# LT1990_Input2.net
KiCad netlist of a schematic drawn in Altium Designer
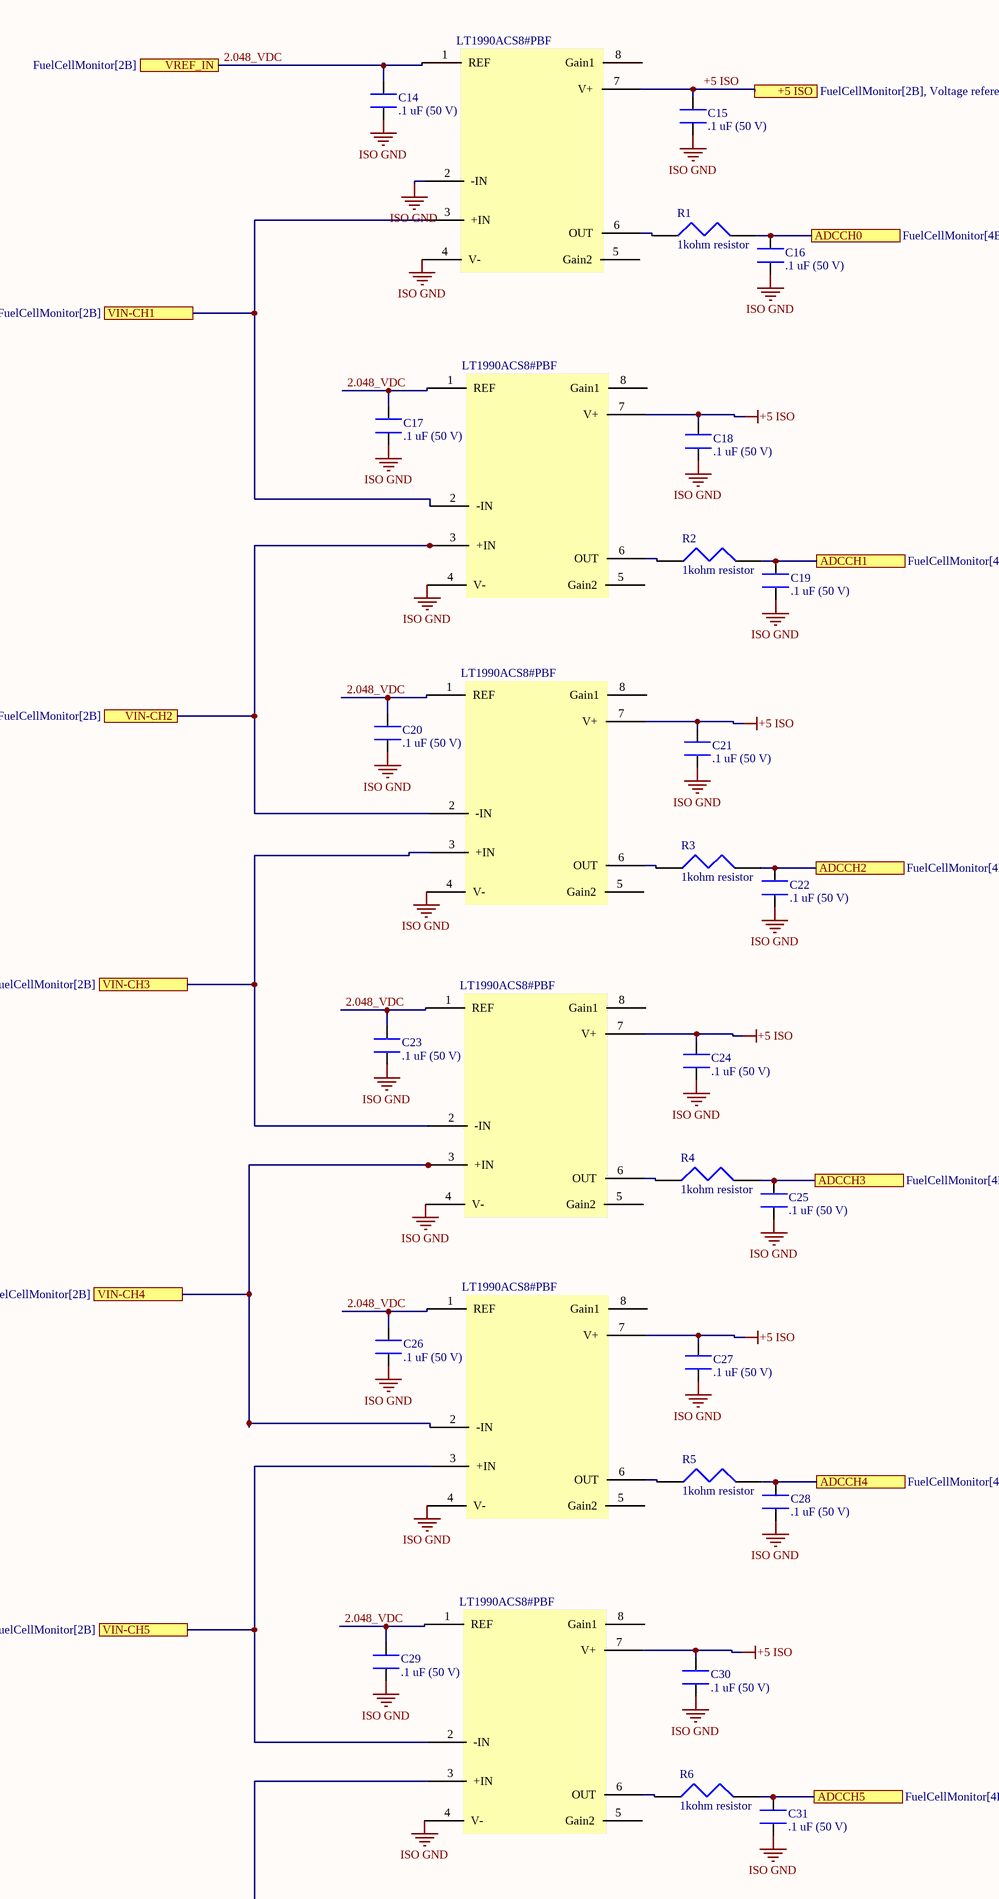
[diagram p0: LT1990(Input2).SchDoc, top left]
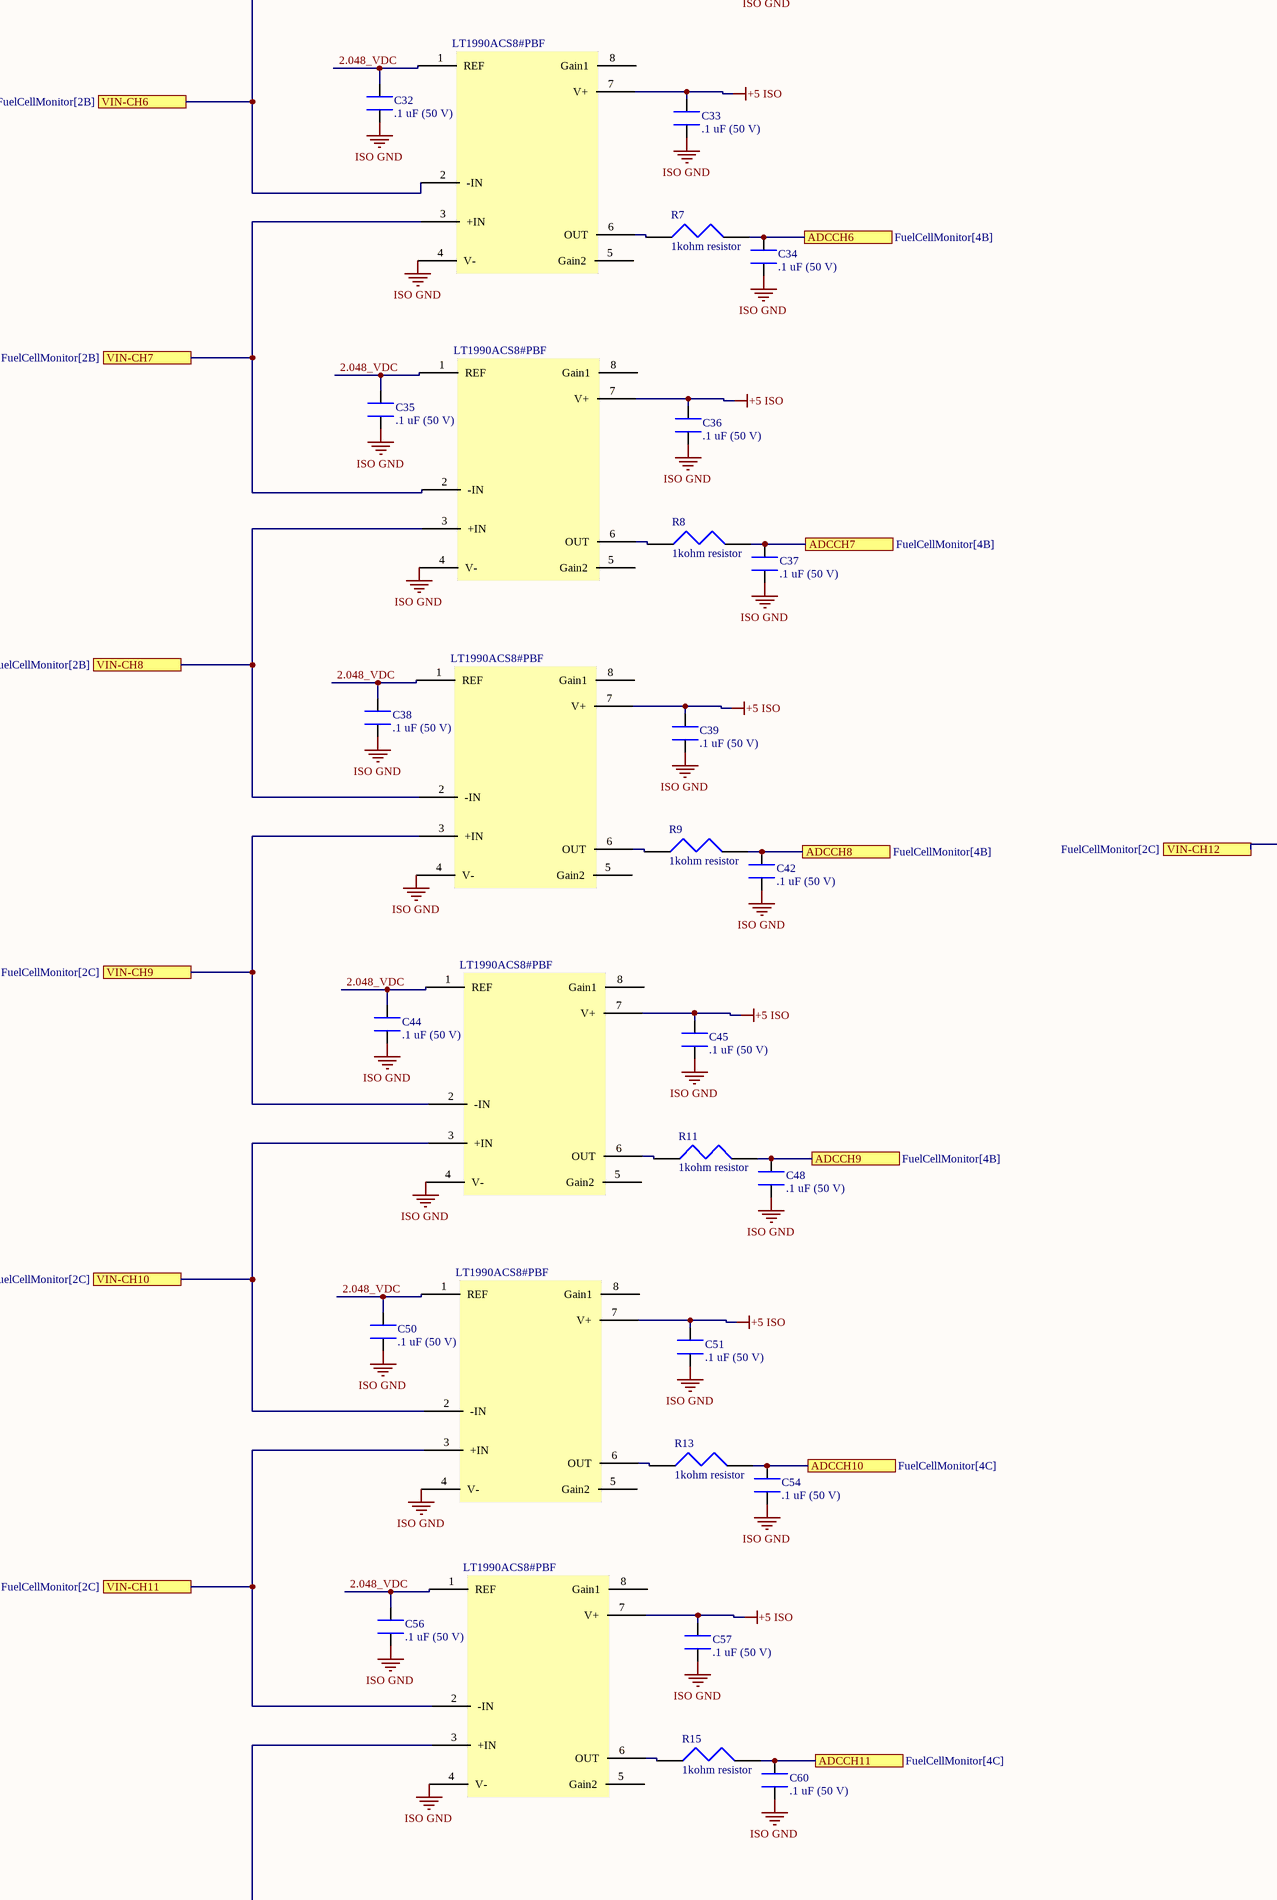
[diagram p1: LT1990(Input2).SchDoc, bottom left]
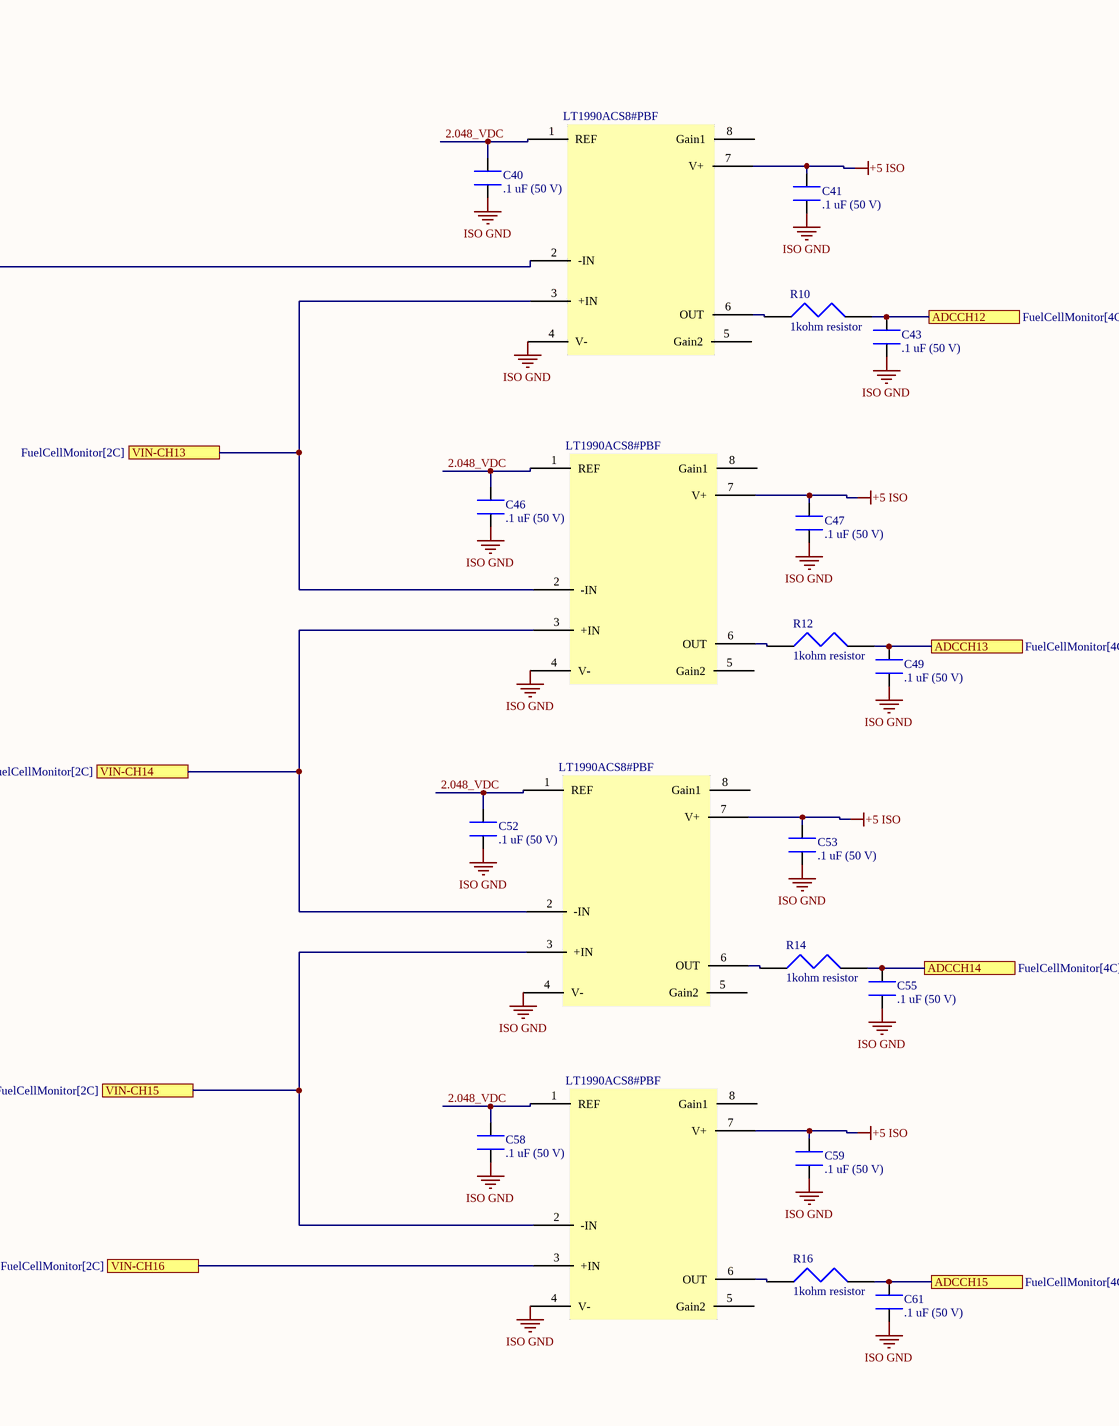
[diagram p2: LT1990(Input2).SchDoc, bottom right]

(export (version "E")
  (design (tool "Eeschema 10.0.6"))
  (components
    (comp (ref "C14")
      (value ".1 uF (50 V)")
      (footprint ".1uF capacitor")
      (libsource (lib "FuelCellMonitor") (part ".1 uF cap"))
    )
    (comp (ref "C15")
      (value ".1 uF (50 V)")
      (footprint ".1uF capacitor")
      (libsource (lib "FuelCellMonitor") (part ".1 uF cap"))
    )
    (comp (ref "C16")
      (value ".1 uF (50 V)")
      (footprint ".1uF capacitor")
      (libsource (lib "FuelCellMonitor") (part ".1 uF cap"))
    )
    (comp (ref "C17")
      (value ".1 uF (50 V)")
      (footprint ".1uF capacitor")
      (libsource (lib "FuelCellMonitor") (part ".1 uF cap"))
    )
    (comp (ref "C18")
      (value ".1 uF (50 V)")
      (footprint ".1uF capacitor")
      (libsource (lib "FuelCellMonitor") (part ".1 uF cap"))
    )
    (comp (ref "C19")
      (value ".1 uF (50 V)")
      (footprint ".1uF capacitor")
      (libsource (lib "FuelCellMonitor") (part ".1 uF cap"))
    )
    (comp (ref "C20")
      (value ".1 uF (50 V)")
      (footprint ".1uF capacitor")
      (libsource (lib "FuelCellMonitor") (part ".1 uF cap"))
    )
    (comp (ref "C21")
      (value ".1 uF (50 V)")
      (footprint ".1uF capacitor")
      (libsource (lib "FuelCellMonitor") (part ".1 uF cap"))
    )
    (comp (ref "C22")
      (value ".1 uF (50 V)")
      (footprint ".1uF capacitor")
      (libsource (lib "FuelCellMonitor") (part ".1 uF cap"))
    )
    (comp (ref "C23")
      (value ".1 uF (50 V)")
      (footprint ".1uF capacitor")
      (libsource (lib "FuelCellMonitor") (part ".1 uF cap"))
    )
    (comp (ref "C24")
      (value ".1 uF (50 V)")
      (footprint ".1uF capacitor")
      (libsource (lib "FuelCellMonitor") (part ".1 uF cap"))
    )
    (comp (ref "C25")
      (value ".1 uF (50 V)")
      (footprint ".1uF capacitor")
      (libsource (lib "FuelCellMonitor") (part ".1 uF cap"))
    )
    (comp (ref "C26")
      (value ".1 uF (50 V)")
      (footprint ".1uF capacitor")
      (libsource (lib "FuelCellMonitor") (part ".1 uF cap"))
    )
    (comp (ref "C27")
      (value ".1 uF (50 V)")
      (footprint ".1uF capacitor")
      (libsource (lib "FuelCellMonitor") (part ".1 uF cap"))
    )
    (comp (ref "C28")
      (value ".1 uF (50 V)")
      (footprint ".1uF capacitor")
      (libsource (lib "FuelCellMonitor") (part ".1 uF cap"))
    )
    (comp (ref "C29")
      (value ".1 uF (50 V)")
      (footprint ".1uF capacitor")
      (libsource (lib "FuelCellMonitor") (part ".1 uF cap"))
    )
    (comp (ref "C30")
      (value ".1 uF (50 V)")
      (footprint ".1uF capacitor")
      (libsource (lib "FuelCellMonitor") (part ".1 uF cap"))
    )
    (comp (ref "C31")
      (value ".1 uF (50 V)")
      (footprint ".1uF capacitor")
      (libsource (lib "FuelCellMonitor") (part ".1 uF cap"))
    )
    (comp (ref "C32")
      (value ".1 uF (50 V)")
      (footprint ".1uF capacitor")
      (libsource (lib "FuelCellMonitor") (part ".1 uF cap"))
    )
    (comp (ref "C33")
      (value ".1 uF (50 V)")
      (footprint ".1uF capacitor")
      (libsource (lib "FuelCellMonitor") (part ".1 uF cap"))
    )
    (comp (ref "C34")
      (value ".1 uF (50 V)")
      (footprint ".1uF capacitor")
      (libsource (lib "FuelCellMonitor") (part ".1 uF cap"))
    )
    (comp (ref "C35")
      (value ".1 uF (50 V)")
      (footprint ".1uF capacitor")
      (libsource (lib "FuelCellMonitor") (part ".1 uF cap"))
    )
    (comp (ref "C36")
      (value ".1 uF (50 V)")
      (footprint ".1uF capacitor")
      (libsource (lib "FuelCellMonitor") (part ".1 uF cap"))
    )
    (comp (ref "C37")
      (value ".1 uF (50 V)")
      (footprint ".1uF capacitor")
      (libsource (lib "FuelCellMonitor") (part ".1 uF cap"))
    )
    (comp (ref "C38")
      (value ".1 uF (50 V)")
      (footprint ".1uF capacitor")
      (libsource (lib "FuelCellMonitor") (part ".1 uF cap"))
    )
    (comp (ref "C39")
      (value ".1 uF (50 V)")
      (footprint ".1uF capacitor")
      (libsource (lib "FuelCellMonitor") (part ".1 uF cap"))
    )
    (comp (ref "C40")
      (value ".1 uF (50 V)")
      (footprint ".1uF capacitor")
      (libsource (lib "FuelCellMonitor") (part ".1 uF cap"))
    )
    (comp (ref "C41")
      (value ".1 uF (50 V)")
      (footprint ".1uF capacitor")
      (libsource (lib "FuelCellMonitor") (part ".1 uF cap"))
    )
    (comp (ref "C42")
      (value ".1 uF (50 V)")
      (footprint ".1uF capacitor")
      (libsource (lib "FuelCellMonitor") (part ".1 uF cap"))
    )
    (comp (ref "C43")
      (value ".1 uF (50 V)")
      (footprint ".1uF capacitor")
      (libsource (lib "FuelCellMonitor") (part ".1 uF cap"))
    )
    (comp (ref "C44")
      (value ".1 uF (50 V)")
      (footprint ".1uF capacitor")
      (libsource (lib "FuelCellMonitor") (part ".1 uF cap"))
    )
    (comp (ref "C45")
      (value ".1 uF (50 V)")
      (footprint ".1uF capacitor")
      (libsource (lib "FuelCellMonitor") (part ".1 uF cap"))
    )
    (comp (ref "C46")
      (value ".1 uF (50 V)")
      (footprint ".1uF capacitor")
      (libsource (lib "FuelCellMonitor") (part ".1 uF cap"))
    )
    (comp (ref "C47")
      (value ".1 uF (50 V)")
      (footprint ".1uF capacitor")
      (libsource (lib "FuelCellMonitor") (part ".1 uF cap"))
    )
    (comp (ref "C48")
      (value ".1 uF (50 V)")
      (footprint ".1uF capacitor")
      (libsource (lib "FuelCellMonitor") (part ".1 uF cap"))
    )
    (comp (ref "C49")
      (value ".1 uF (50 V)")
      (footprint ".1uF capacitor")
      (libsource (lib "FuelCellMonitor") (part ".1 uF cap"))
    )
    (comp (ref "C50")
      (value ".1 uF (50 V)")
      (footprint ".1uF capacitor")
      (libsource (lib "FuelCellMonitor") (part ".1 uF cap"))
    )
    (comp (ref "C51")
      (value ".1 uF (50 V)")
      (footprint ".1uF capacitor")
      (libsource (lib "FuelCellMonitor") (part ".1 uF cap"))
    )
    (comp (ref "C52")
      (value ".1 uF (50 V)")
      (footprint ".1uF capacitor")
      (libsource (lib "FuelCellMonitor") (part ".1 uF cap"))
    )
    (comp (ref "C53")
      (value ".1 uF (50 V)")
      (footprint ".1uF capacitor")
      (libsource (lib "FuelCellMonitor") (part ".1 uF cap"))
    )
    (comp (ref "C54")
      (value ".1 uF (50 V)")
      (footprint ".1uF capacitor")
      (libsource (lib "FuelCellMonitor") (part ".1 uF cap"))
    )
    (comp (ref "C55")
      (value ".1 uF (50 V)")
      (footprint ".1uF capacitor")
      (libsource (lib "FuelCellMonitor") (part ".1 uF cap"))
    )
    (comp (ref "C56")
      (value ".1 uF (50 V)")
      (footprint ".1uF capacitor")
      (libsource (lib "FuelCellMonitor") (part ".1 uF cap"))
    )
    (comp (ref "C57")
      (value ".1 uF (50 V)")
      (footprint ".1uF capacitor")
      (libsource (lib "FuelCellMonitor") (part ".1 uF cap"))
    )
    (comp (ref "C58")
      (value ".1 uF (50 V)")
      (footprint ".1uF capacitor")
      (libsource (lib "FuelCellMonitor") (part ".1 uF cap"))
    )
    (comp (ref "C59")
      (value ".1 uF (50 V)")
      (footprint ".1uF capacitor")
      (libsource (lib "FuelCellMonitor") (part ".1 uF cap"))
    )
    (comp (ref "C60")
      (value ".1 uF (50 V)")
      (footprint ".1uF capacitor")
      (libsource (lib "FuelCellMonitor") (part ".1 uF cap"))
    )
    (comp (ref "C61")
      (value ".1 uF (50 V)")
      (footprint ".1uF capacitor")
      (libsource (lib "FuelCellMonitor") (part ".1 uF cap"))
    )
    (comp (ref "LT1")
      (value "LT1990")
      (footprint "LT1990ACS8")
      (libsource (lib "FuelCellMonitor") (part "LT1990"))
    )
    (comp (ref "LT2")
      (value "LT1990")
      (footprint "LT1990ACS8")
      (libsource (lib "FuelCellMonitor") (part "LT1990"))
    )
    (comp (ref "LT3")
      (value "LT1990")
      (footprint "LT1990ACS8")
      (libsource (lib "FuelCellMonitor") (part "LT1990"))
    )
    (comp (ref "LT4")
      (value "LT1990")
      (footprint "LT1990ACS8")
      (libsource (lib "FuelCellMonitor") (part "LT1990"))
    )
    (comp (ref "LT5")
      (value "LT1990")
      (footprint "LT1990ACS8")
      (libsource (lib "FuelCellMonitor") (part "LT1990"))
    )
    (comp (ref "LT6")
      (value "LT1990")
      (footprint "LT1990ACS8")
      (libsource (lib "FuelCellMonitor") (part "LT1990"))
    )
    (comp (ref "LT7")
      (value "LT1990")
      (footprint "LT1990ACS8")
      (libsource (lib "FuelCellMonitor") (part "LT1990"))
    )
    (comp (ref "LT8")
      (value "LT1990")
      (footprint "LT1990ACS8")
      (libsource (lib "FuelCellMonitor") (part "LT1990"))
    )
    (comp (ref "LT9")
      (value "LT1990")
      (footprint "LT1990ACS8")
      (libsource (lib "FuelCellMonitor") (part "LT1990"))
    )
    (comp (ref "LT10")
      (value "LT1990")
      (footprint "LT1990ACS8")
      (libsource (lib "FuelCellMonitor") (part "LT1990"))
    )
    (comp (ref "LT11")
      (value "LT1990")
      (footprint "LT1990ACS8")
      (libsource (lib "FuelCellMonitor") (part "LT1990"))
    )
    (comp (ref "LT12")
      (value "LT1990")
      (footprint "LT1990ACS8")
      (libsource (lib "FuelCellMonitor") (part "LT1990"))
    )
    (comp (ref "LT13")
      (value "LT1990")
      (footprint "LT1990ACS8")
      (libsource (lib "FuelCellMonitor") (part "LT1990"))
    )
    (comp (ref "LT14")
      (value "LT1990")
      (footprint "LT1990ACS8")
      (libsource (lib "FuelCellMonitor") (part "LT1990"))
    )
    (comp (ref "LT15")
      (value "LT1990")
      (footprint "LT1990ACS8")
      (libsource (lib "FuelCellMonitor") (part "LT1990"))
    )
    (comp (ref "LT16")
      (value "LT1990")
      (footprint "LT1990ACS8")
      (libsource (lib "FuelCellMonitor") (part "LT1990"))
    )
    (comp (ref "R1")
      (value "1kohm resistor")
      (footprint "1kohm resistor")
      (libsource (lib "FuelCellMonitor") (part "1kohm resistor"))
    )
    (comp (ref "R2")
      (value "1kohm resistor")
      (footprint "1kohm resistor")
      (libsource (lib "FuelCellMonitor") (part "1kohm resistor"))
    )
    (comp (ref "R3")
      (value "1kohm resistor")
      (footprint "1kohm resistor")
      (libsource (lib "FuelCellMonitor") (part "1kohm resistor"))
    )
    (comp (ref "R4")
      (value "1kohm resistor")
      (footprint "1kohm resistor")
      (libsource (lib "FuelCellMonitor") (part "1kohm resistor"))
    )
    (comp (ref "R5")
      (value "1kohm resistor")
      (footprint "1kohm resistor")
      (libsource (lib "FuelCellMonitor") (part "1kohm resistor"))
    )
    (comp (ref "R6")
      (value "1kohm resistor")
      (footprint "1kohm resistor")
      (libsource (lib "FuelCellMonitor") (part "1kohm resistor"))
    )
    (comp (ref "R7")
      (value "1kohm resistor")
      (footprint "1kohm resistor")
      (libsource (lib "FuelCellMonitor") (part "1kohm resistor"))
    )
    (comp (ref "R8")
      (value "1kohm resistor")
      (footprint "1kohm resistor")
      (libsource (lib "FuelCellMonitor") (part "1kohm resistor"))
    )
    (comp (ref "R9")
      (value "1kohm resistor")
      (footprint "1kohm resistor")
      (libsource (lib "FuelCellMonitor") (part "1kohm resistor"))
    )
    (comp (ref "R10")
      (value "1kohm resistor")
      (footprint "1kohm resistor")
      (libsource (lib "FuelCellMonitor") (part "1kohm resistor"))
    )
    (comp (ref "R11")
      (value "1kohm resistor")
      (footprint "1kohm resistor")
      (libsource (lib "FuelCellMonitor") (part "1kohm resistor"))
    )
    (comp (ref "R12")
      (value "1kohm resistor")
      (footprint "1kohm resistor")
      (libsource (lib "FuelCellMonitor") (part "1kohm resistor"))
    )
    (comp (ref "R13")
      (value "1kohm resistor")
      (footprint "1kohm resistor")
      (libsource (lib "FuelCellMonitor") (part "1kohm resistor"))
    )
    (comp (ref "R14")
      (value "1kohm resistor")
      (footprint "1kohm resistor")
      (libsource (lib "FuelCellMonitor") (part "1kohm resistor"))
    )
    (comp (ref "R15")
      (value "1kohm resistor")
      (footprint "1kohm resistor")
      (libsource (lib "FuelCellMonitor") (part "1kohm resistor"))
    )
    (comp (ref "R16")
      (value "1kohm resistor")
      (footprint "1kohm resistor")
      (libsource (lib "FuelCellMonitor") (part "1kohm resistor"))
    )
  )
  (nets
    (net (code "1") (name "+5 ISO") (class "Default")
      (node (ref "C15") (pin "2") (pinfunction "2_2") (pintype "power_in"))
      (node (ref "C18") (pin "2") (pinfunction "2_2") (pintype "power_in"))
      (node (ref "C21") (pin "2") (pinfunction "2_2") (pintype "power_in"))
      (node (ref "C24") (pin "2") (pinfunction "2_2") (pintype "power_in"))
      (node (ref "C27") (pin "2") (pinfunction "2_2") (pintype "power_in"))
      (node (ref "C30") (pin "2") (pinfunction "2_2") (pintype "power_in"))
      (node (ref "C33") (pin "2") (pinfunction "2_2") (pintype "power_in"))
      (node (ref "C36") (pin "2") (pinfunction "2_2") (pintype "power_in"))
      (node (ref "C39") (pin "2") (pinfunction "2_2") (pintype "power_in"))
      (node (ref "C41") (pin "2") (pinfunction "2_2") (pintype "power_in"))
      (node (ref "C45") (pin "2") (pinfunction "2_2") (pintype "power_in"))
      (node (ref "C47") (pin "2") (pinfunction "2_2") (pintype "power_in"))
      (node (ref "C51") (pin "2") (pinfunction "2_2") (pintype "power_in"))
      (node (ref "C53") (pin "2") (pinfunction "2_2") (pintype "power_in"))
      (node (ref "C57") (pin "2") (pinfunction "2_2") (pintype "power_in"))
      (node (ref "C59") (pin "2") (pinfunction "2_2") (pintype "power_in"))
      (node (ref "LT1") (pin "7") (pinfunction "V+_7") (pintype "passive"))
      (node (ref "LT10") (pin "7") (pinfunction "V+_7") (pintype "passive"))
      (node (ref "LT11") (pin "7") (pinfunction "V+_7") (pintype "passive"))
      (node (ref "LT12") (pin "7") (pinfunction "V+_7") (pintype "passive"))
      (node (ref "LT13") (pin "7") (pinfunction "V+_7") (pintype "passive"))
      (node (ref "LT14") (pin "7") (pinfunction "V+_7") (pintype "passive"))
      (node (ref "LT15") (pin "7") (pinfunction "V+_7") (pintype "passive"))
      (node (ref "LT16") (pin "7") (pinfunction "V+_7") (pintype "passive"))
      (node (ref "LT2") (pin "7") (pinfunction "V+_7") (pintype "passive"))
      (node (ref "LT3") (pin "7") (pinfunction "V+_7") (pintype "passive"))
      (node (ref "LT4") (pin "7") (pinfunction "V+_7") (pintype "passive"))
      (node (ref "LT5") (pin "7") (pinfunction "V+_7") (pintype "passive"))
      (node (ref "LT6") (pin "7") (pinfunction "V+_7") (pintype "passive"))
      (node (ref "LT7") (pin "7") (pinfunction "V+_7") (pintype "passive"))
      (node (ref "LT8") (pin "7") (pinfunction "V+_7") (pintype "passive"))
      (node (ref "LT9") (pin "7") (pinfunction "V+_7") (pintype "passive"))
    )
    (net (code "2") (name "/2.048_VDC") (class "Default")
      (node (ref "C14") (pin "2") (pinfunction "2_2") (pintype "power_in"))
      (node (ref "C17") (pin "2") (pinfunction "2_2") (pintype "power_in"))
      (node (ref "C20") (pin "2") (pinfunction "2_2") (pintype "power_in"))
      (node (ref "C23") (pin "2") (pinfunction "2_2") (pintype "power_in"))
      (node (ref "C26") (pin "2") (pinfunction "2_2") (pintype "power_in"))
      (node (ref "C29") (pin "2") (pinfunction "2_2") (pintype "power_in"))
      (node (ref "C32") (pin "2") (pinfunction "2_2") (pintype "power_in"))
      (node (ref "C35") (pin "2") (pinfunction "2_2") (pintype "power_in"))
      (node (ref "C38") (pin "2") (pinfunction "2_2") (pintype "power_in"))
      (node (ref "C40") (pin "2") (pinfunction "2_2") (pintype "power_in"))
      (node (ref "C44") (pin "2") (pinfunction "2_2") (pintype "power_in"))
      (node (ref "C46") (pin "2") (pinfunction "2_2") (pintype "power_in"))
      (node (ref "C50") (pin "2") (pinfunction "2_2") (pintype "power_in"))
      (node (ref "C52") (pin "2") (pinfunction "2_2") (pintype "power_in"))
      (node (ref "C56") (pin "2") (pinfunction "2_2") (pintype "power_in"))
      (node (ref "C58") (pin "2") (pinfunction "2_2") (pintype "power_in"))
      (node (ref "LT1") (pin "1") (pinfunction "REF_1") (pintype "passive"))
      (node (ref "LT10") (pin "1") (pinfunction "REF_1") (pintype "passive"))
      (node (ref "LT11") (pin "1") (pinfunction "REF_1") (pintype "passive"))
      (node (ref "LT12") (pin "1") (pinfunction "REF_1") (pintype "passive"))
      (node (ref "LT13") (pin "1") (pinfunction "REF_1") (pintype "passive"))
      (node (ref "LT14") (pin "1") (pinfunction "REF_1") (pintype "passive"))
      (node (ref "LT15") (pin "1") (pinfunction "REF_1") (pintype "passive"))
      (node (ref "LT16") (pin "1") (pinfunction "REF_1") (pintype "passive"))
      (node (ref "LT2") (pin "1") (pinfunction "REF_1") (pintype "passive"))
      (node (ref "LT3") (pin "1") (pinfunction "REF_1") (pintype "passive"))
      (node (ref "LT4") (pin "1") (pinfunction "REF_1") (pintype "passive"))
      (node (ref "LT5") (pin "1") (pinfunction "REF_1") (pintype "passive"))
      (node (ref "LT6") (pin "1") (pinfunction "REF_1") (pintype "passive"))
      (node (ref "LT7") (pin "1") (pinfunction "REF_1") (pintype "passive"))
      (node (ref "LT8") (pin "1") (pinfunction "REF_1") (pintype "passive"))
      (node (ref "LT9") (pin "1") (pinfunction "REF_1") (pintype "passive"))
    )
    (net (code "3") (name "/ADCCH0") (class "Default")
      (node (ref "C16") (pin "2") (pinfunction "2_2") (pintype "power_in"))
      (node (ref "R1") (pin "2") (pinfunction "2_2") (pintype "passive"))
    )
    (net (code "4") (name "/ADCCH1") (class "Default")
      (node (ref "C19") (pin "2") (pinfunction "2_2") (pintype "power_in"))
      (node (ref "R2") (pin "2") (pinfunction "2_2") (pintype "passive"))
    )
    (net (code "5") (name "/ADCCH2") (class "Default")
      (node (ref "C22") (pin "2") (pinfunction "2_2") (pintype "power_in"))
      (node (ref "R3") (pin "2") (pinfunction "2_2") (pintype "passive"))
    )
    (net (code "6") (name "/ADCCH3") (class "Default")
      (node (ref "C25") (pin "2") (pinfunction "2_2") (pintype "power_in"))
      (node (ref "R4") (pin "2") (pinfunction "2_2") (pintype "passive"))
    )
    (net (code "7") (name "/ADCCH4") (class "Default")
      (node (ref "C28") (pin "2") (pinfunction "2_2") (pintype "power_in"))
      (node (ref "R5") (pin "2") (pinfunction "2_2") (pintype "passive"))
    )
    (net (code "8") (name "/ADCCH5") (class "Default")
      (node (ref "C31") (pin "2") (pinfunction "2_2") (pintype "power_in"))
      (node (ref "R6") (pin "2") (pinfunction "2_2") (pintype "passive"))
    )
    (net (code "9") (name "/ADCCH6") (class "Default")
      (node (ref "C34") (pin "2") (pinfunction "2_2") (pintype "power_in"))
      (node (ref "R7") (pin "2") (pinfunction "2_2") (pintype "passive"))
    )
    (net (code "10") (name "/ADCCH7") (class "Default")
      (node (ref "C37") (pin "2") (pinfunction "2_2") (pintype "power_in"))
      (node (ref "R8") (pin "2") (pinfunction "2_2") (pintype "passive"))
    )
    (net (code "11") (name "/ADCCH8") (class "Default")
      (node (ref "C42") (pin "2") (pinfunction "2_2") (pintype "power_in"))
      (node (ref "R9") (pin "2") (pinfunction "2_2") (pintype "passive"))
    )
    (net (code "12") (name "/ADCCH9") (class "Default")
      (node (ref "C48") (pin "2") (pinfunction "2_2") (pintype "power_in"))
      (node (ref "R11") (pin "2") (pinfunction "2_2") (pintype "passive"))
    )
    (net (code "13") (name "/ADCCH10") (class "Default")
      (node (ref "C54") (pin "2") (pinfunction "2_2") (pintype "power_in"))
      (node (ref "R13") (pin "2") (pinfunction "2_2") (pintype "passive"))
    )
    (net (code "14") (name "/ADCCH11") (class "Default")
      (node (ref "C60") (pin "2") (pinfunction "2_2") (pintype "power_in"))
      (node (ref "R15") (pin "2") (pinfunction "2_2") (pintype "passive"))
    )
    (net (code "15") (name "/ADCCH12") (class "Default")
      (node (ref "C43") (pin "2") (pinfunction "2_2") (pintype "power_in"))
      (node (ref "R10") (pin "2") (pinfunction "2_2") (pintype "passive"))
    )
    (net (code "16") (name "/ADCCH13") (class "Default")
      (node (ref "C49") (pin "2") (pinfunction "2_2") (pintype "power_in"))
      (node (ref "R12") (pin "2") (pinfunction "2_2") (pintype "passive"))
    )
    (net (code "17") (name "/ADCCH14") (class "Default")
      (node (ref "C55") (pin "2") (pinfunction "2_2") (pintype "power_in"))
      (node (ref "R14") (pin "2") (pinfunction "2_2") (pintype "passive"))
    )
    (net (code "18") (name "/ADCCH15") (class "Default")
      (node (ref "C61") (pin "2") (pinfunction "2_2") (pintype "power_in"))
      (node (ref "R16") (pin "2") (pinfunction "2_2") (pintype "passive"))
    )
    (net (code "19") (name "/VIN-CH1") (class "Default")
      (node (ref "LT1") (pin "3") (pinfunction "+IN_3") (pintype "passive"))
      (node (ref "LT2") (pin "2") (pinfunction "-IN_2") (pintype "passive"))
    )
    (net (code "20") (name "/VIN-CH2") (class "Default")
      (node (ref "LT2") (pin "3") (pinfunction "+IN_3") (pintype "passive"))
      (node (ref "LT3") (pin "2") (pinfunction "-IN_2") (pintype "passive"))
    )
    (net (code "21") (name "/VIN-CH3") (class "Default")
      (node (ref "LT3") (pin "3") (pinfunction "+IN_3") (pintype "passive"))
      (node (ref "LT4") (pin "2") (pinfunction "-IN_2") (pintype "passive"))
    )
    (net (code "22") (name "/VIN-CH4") (class "Default")
      (node (ref "LT4") (pin "3") (pinfunction "+IN_3") (pintype "passive"))
      (node (ref "LT5") (pin "2") (pinfunction "-IN_2") (pintype "passive"))
    )
    (net (code "23") (name "/VIN-CH5") (class "Default")
      (node (ref "LT5") (pin "3") (pinfunction "+IN_3") (pintype "passive"))
      (node (ref "LT6") (pin "2") (pinfunction "-IN_2") (pintype "passive"))
    )
    (net (code "24") (name "/VIN-CH6") (class "Default")
      (node (ref "LT6") (pin "3") (pinfunction "+IN_3") (pintype "passive"))
      (node (ref "LT7") (pin "2") (pinfunction "-IN_2") (pintype "passive"))
    )
    (net (code "25") (name "/VIN-CH7") (class "Default")
      (node (ref "LT7") (pin "3") (pinfunction "+IN_3") (pintype "passive"))
      (node (ref "LT8") (pin "2") (pinfunction "-IN_2") (pintype "passive"))
    )
    (net (code "26") (name "/VIN-CH8") (class "Default")
      (node (ref "LT8") (pin "3") (pinfunction "+IN_3") (pintype "passive"))
      (node (ref "LT9") (pin "2") (pinfunction "-IN_2") (pintype "passive"))
    )
    (net (code "27") (name "/VIN-CH9") (class "Default")
      (node (ref "LT10") (pin "2") (pinfunction "-IN_2") (pintype "passive"))
      (node (ref "LT9") (pin "3") (pinfunction "+IN_3") (pintype "passive"))
    )
    (net (code "28") (name "/VIN-CH10") (class "Default")
      (node (ref "LT10") (pin "3") (pinfunction "+IN_3") (pintype "passive"))
      (node (ref "LT11") (pin "2") (pinfunction "-IN_2") (pintype "passive"))
    )
    (net (code "29") (name "/VIN-CH11") (class "Default")
      (node (ref "LT11") (pin "3") (pinfunction "+IN_3") (pintype "passive"))
      (node (ref "LT12") (pin "2") (pinfunction "-IN_2") (pintype "passive"))
    )
    (net (code "30") (name "/VIN-CH12") (class "Default")
      (node (ref "LT12") (pin "3") (pinfunction "+IN_3") (pintype "passive"))
      (node (ref "LT13") (pin "2") (pinfunction "-IN_2") (pintype "passive"))
    )
    (net (code "31") (name "/VIN-CH13") (class "Default")
      (node (ref "LT13") (pin "3") (pinfunction "+IN_3") (pintype "passive"))
      (node (ref "LT14") (pin "2") (pinfunction "-IN_2") (pintype "passive"))
    )
    (net (code "32") (name "/VIN-CH14") (class "Default")
      (node (ref "LT14") (pin "3") (pinfunction "+IN_3") (pintype "passive"))
      (node (ref "LT15") (pin "2") (pinfunction "-IN_2") (pintype "passive"))
    )
    (net (code "33") (name "/VIN-CH15") (class "Default")
      (node (ref "LT15") (pin "3") (pinfunction "+IN_3") (pintype "passive"))
      (node (ref "LT16") (pin "2") (pinfunction "-IN_2") (pintype "passive"))
    )
    (net (code "34") (name "/VIN-CH16") (class "Default")
      (node (ref "LT16") (pin "3") (pinfunction "+IN_3") (pintype "passive"))
    )
    (net (code "35") (name "ISO GND") (class "Default")
      (node (ref "C14") (pin "1") (pinfunction "1_1") (pintype "power_in"))
      (node (ref "C15") (pin "1") (pinfunction "1_1") (pintype "power_in"))
      (node (ref "C16") (pin "1") (pinfunction "1_1") (pintype "power_in"))
      (node (ref "C17") (pin "1") (pinfunction "1_1") (pintype "power_in"))
      (node (ref "C18") (pin "1") (pinfunction "1_1") (pintype "power_in"))
      (node (ref "C19") (pin "1") (pinfunction "1_1") (pintype "power_in"))
      (node (ref "C20") (pin "1") (pinfunction "1_1") (pintype "power_in"))
      (node (ref "C21") (pin "1") (pinfunction "1_1") (pintype "power_in"))
      (node (ref "C22") (pin "1") (pinfunction "1_1") (pintype "power_in"))
      (node (ref "C23") (pin "1") (pinfunction "1_1") (pintype "power_in"))
      (node (ref "C24") (pin "1") (pinfunction "1_1") (pintype "power_in"))
      (node (ref "C25") (pin "1") (pinfunction "1_1") (pintype "power_in"))
      (node (ref "C26") (pin "1") (pinfunction "1_1") (pintype "power_in"))
      (node (ref "C27") (pin "1") (pinfunction "1_1") (pintype "power_in"))
      (node (ref "C28") (pin "1") (pinfunction "1_1") (pintype "power_in"))
      (node (ref "C29") (pin "1") (pinfunction "1_1") (pintype "power_in"))
      (node (ref "C30") (pin "1") (pinfunction "1_1") (pintype "power_in"))
      (node (ref "C31") (pin "1") (pinfunction "1_1") (pintype "power_in"))
      (node (ref "C32") (pin "1") (pinfunction "1_1") (pintype "power_in"))
      (node (ref "C33") (pin "1") (pinfunction "1_1") (pintype "power_in"))
      (node (ref "C34") (pin "1") (pinfunction "1_1") (pintype "power_in"))
      (node (ref "C35") (pin "1") (pinfunction "1_1") (pintype "power_in"))
      (node (ref "C36") (pin "1") (pinfunction "1_1") (pintype "power_in"))
      (node (ref "C37") (pin "1") (pinfunction "1_1") (pintype "power_in"))
      (node (ref "C38") (pin "1") (pinfunction "1_1") (pintype "power_in"))
      (node (ref "C39") (pin "1") (pinfunction "1_1") (pintype "power_in"))
      (node (ref "C40") (pin "1") (pinfunction "1_1") (pintype "power_in"))
      (node (ref "C41") (pin "1") (pinfunction "1_1") (pintype "power_in"))
      (node (ref "C42") (pin "1") (pinfunction "1_1") (pintype "power_in"))
      (node (ref "C43") (pin "1") (pinfunction "1_1") (pintype "power_in"))
      (node (ref "C44") (pin "1") (pinfunction "1_1") (pintype "power_in"))
      (node (ref "C45") (pin "1") (pinfunction "1_1") (pintype "power_in"))
      (node (ref "C46") (pin "1") (pinfunction "1_1") (pintype "power_in"))
      (node (ref "C47") (pin "1") (pinfunction "1_1") (pintype "power_in"))
      (node (ref "C48") (pin "1") (pinfunction "1_1") (pintype "power_in"))
      (node (ref "C49") (pin "1") (pinfunction "1_1") (pintype "power_in"))
      (node (ref "C50") (pin "1") (pinfunction "1_1") (pintype "power_in"))
      (node (ref "C51") (pin "1") (pinfunction "1_1") (pintype "power_in"))
      (node (ref "C52") (pin "1") (pinfunction "1_1") (pintype "power_in"))
      (node (ref "C53") (pin "1") (pinfunction "1_1") (pintype "power_in"))
      (node (ref "C54") (pin "1") (pinfunction "1_1") (pintype "power_in"))
      (node (ref "C55") (pin "1") (pinfunction "1_1") (pintype "power_in"))
      (node (ref "C56") (pin "1") (pinfunction "1_1") (pintype "power_in"))
      (node (ref "C57") (pin "1") (pinfunction "1_1") (pintype "power_in"))
      (node (ref "C58") (pin "1") (pinfunction "1_1") (pintype "power_in"))
      (node (ref "C59") (pin "1") (pinfunction "1_1") (pintype "power_in"))
      (node (ref "C60") (pin "1") (pinfunction "1_1") (pintype "power_in"))
      (node (ref "C61") (pin "1") (pinfunction "1_1") (pintype "power_in"))
      (node (ref "LT1") (pin "2") (pinfunction "-IN_2") (pintype "passive"))
      (node (ref "LT1") (pin "4") (pinfunction "V-_4") (pintype "passive"))
      (node (ref "LT10") (pin "4") (pinfunction "V-_4") (pintype "passive"))
      (node (ref "LT11") (pin "4") (pinfunction "V-_4") (pintype "passive"))
      (node (ref "LT12") (pin "4") (pinfunction "V-_4") (pintype "passive"))
      (node (ref "LT13") (pin "4") (pinfunction "V-_4") (pintype "passive"))
      (node (ref "LT14") (pin "4") (pinfunction "V-_4") (pintype "passive"))
      (node (ref "LT15") (pin "4") (pinfunction "V-_4") (pintype "passive"))
      (node (ref "LT16") (pin "4") (pinfunction "V-_4") (pintype "passive"))
      (node (ref "LT2") (pin "4") (pinfunction "V-_4") (pintype "passive"))
      (node (ref "LT3") (pin "4") (pinfunction "V-_4") (pintype "passive"))
      (node (ref "LT4") (pin "4") (pinfunction "V-_4") (pintype "passive"))
      (node (ref "LT5") (pin "4") (pinfunction "V-_4") (pintype "passive"))
      (node (ref "LT6") (pin "4") (pinfunction "V-_4") (pintype "passive"))
      (node (ref "LT7") (pin "4") (pinfunction "V-_4") (pintype "passive"))
      (node (ref "LT8") (pin "4") (pinfunction "V-_4") (pintype "passive"))
      (node (ref "LT9") (pin "4") (pinfunction "V-_4") (pintype "passive"))
    )
    (net (code "36") (name "Net-(LT1-OUT)") (class "Default")
      (node (ref "LT1") (pin "6") (pinfunction "OUT_6") (pintype "passive"))
      (node (ref "R1") (pin "1") (pinfunction "1_1") (pintype "passive"))
    )
    (net (code "37") (name "Net-(LT2-OUT)") (class "Default")
      (node (ref "LT2") (pin "6") (pinfunction "OUT_6") (pintype "passive"))
      (node (ref "R2") (pin "1") (pinfunction "1_1") (pintype "passive"))
    )
    (net (code "38") (name "Net-(LT3-OUT)") (class "Default")
      (node (ref "LT3") (pin "6") (pinfunction "OUT_6") (pintype "passive"))
      (node (ref "R3") (pin "1") (pinfunction "1_1") (pintype "passive"))
    )
    (net (code "39") (name "Net-(LT4-OUT)") (class "Default")
      (node (ref "LT4") (pin "6") (pinfunction "OUT_6") (pintype "passive"))
      (node (ref "R4") (pin "1") (pinfunction "1_1") (pintype "passive"))
    )
    (net (code "40") (name "Net-(LT5-OUT)") (class "Default")
      (node (ref "LT5") (pin "6") (pinfunction "OUT_6") (pintype "passive"))
      (node (ref "R5") (pin "1") (pinfunction "1_1") (pintype "passive"))
    )
    (net (code "41") (name "Net-(LT6-OUT)") (class "Default")
      (node (ref "LT6") (pin "6") (pinfunction "OUT_6") (pintype "passive"))
      (node (ref "R6") (pin "1") (pinfunction "1_1") (pintype "passive"))
    )
    (net (code "42") (name "Net-(LT7-OUT)") (class "Default")
      (node (ref "LT7") (pin "6") (pinfunction "OUT_6") (pintype "passive"))
      (node (ref "R7") (pin "1") (pinfunction "1_1") (pintype "passive"))
    )
    (net (code "43") (name "Net-(LT8-OUT)") (class "Default")
      (node (ref "LT8") (pin "6") (pinfunction "OUT_6") (pintype "passive"))
      (node (ref "R8") (pin "1") (pinfunction "1_1") (pintype "passive"))
    )
    (net (code "44") (name "Net-(LT9-OUT)") (class "Default")
      (node (ref "LT9") (pin "6") (pinfunction "OUT_6") (pintype "passive"))
      (node (ref "R9") (pin "1") (pinfunction "1_1") (pintype "passive"))
    )
    (net (code "45") (name "Net-(LT10-OUT)") (class "Default")
      (node (ref "LT10") (pin "6") (pinfunction "OUT_6") (pintype "passive"))
      (node (ref "R11") (pin "1") (pinfunction "1_1") (pintype "passive"))
    )
    (net (code "46") (name "Net-(LT11-OUT)") (class "Default")
      (node (ref "LT11") (pin "6") (pinfunction "OUT_6") (pintype "passive"))
      (node (ref "R13") (pin "1") (pinfunction "1_1") (pintype "passive"))
    )
    (net (code "47") (name "Net-(LT12-OUT)") (class "Default")
      (node (ref "LT12") (pin "6") (pinfunction "OUT_6") (pintype "passive"))
      (node (ref "R15") (pin "1") (pinfunction "1_1") (pintype "passive"))
    )
    (net (code "48") (name "Net-(LT13-OUT)") (class "Default")
      (node (ref "LT13") (pin "6") (pinfunction "OUT_6") (pintype "passive"))
      (node (ref "R10") (pin "1") (pinfunction "1_1") (pintype "passive"))
    )
    (net (code "49") (name "Net-(LT14-OUT)") (class "Default")
      (node (ref "LT14") (pin "6") (pinfunction "OUT_6") (pintype "passive"))
      (node (ref "R12") (pin "1") (pinfunction "1_1") (pintype "passive"))
    )
    (net (code "50") (name "Net-(LT15-OUT)") (class "Default")
      (node (ref "LT15") (pin "6") (pinfunction "OUT_6") (pintype "passive"))
      (node (ref "R14") (pin "1") (pinfunction "1_1") (pintype "passive"))
    )
    (net (code "51") (name "Net-(LT16-OUT)") (class "Default")
      (node (ref "LT16") (pin "6") (pinfunction "OUT_6") (pintype "passive"))
      (node (ref "R16") (pin "1") (pinfunction "1_1") (pintype "passive"))
    )
    (net (code "52") (name "unconnected-(LT1-Gain1-Pad8)") (class "Default")
      (node (ref "LT1") (pin "8") (pinfunction "Gain1_8") (pintype "passive"))
    )
    (net (code "53") (name "unconnected-(LT1-Gain2-Pad5)") (class "Default")
      (node (ref "LT1") (pin "5") (pinfunction "Gain2_5") (pintype "passive"))
    )
    (net (code "54") (name "unconnected-(LT2-Gain1-Pad8)") (class "Default")
      (node (ref "LT2") (pin "8") (pinfunction "Gain1_8") (pintype "passive"))
    )
    (net (code "55") (name "unconnected-(LT2-Gain2-Pad5)") (class "Default")
      (node (ref "LT2") (pin "5") (pinfunction "Gain2_5") (pintype "passive"))
    )
    (net (code "56") (name "unconnected-(LT3-Gain1-Pad8)") (class "Default")
      (node (ref "LT3") (pin "8") (pinfunction "Gain1_8") (pintype "passive"))
    )
    (net (code "57") (name "unconnected-(LT3-Gain2-Pad5)") (class "Default")
      (node (ref "LT3") (pin "5") (pinfunction "Gain2_5") (pintype "passive"))
    )
    (net (code "58") (name "unconnected-(LT4-Gain1-Pad8)") (class "Default")
      (node (ref "LT4") (pin "8") (pinfunction "Gain1_8") (pintype "passive"))
    )
    (net (code "59") (name "unconnected-(LT4-Gain2-Pad5)") (class "Default")
      (node (ref "LT4") (pin "5") (pinfunction "Gain2_5") (pintype "passive"))
    )
    (net (code "60") (name "unconnected-(LT5-Gain1-Pad8)") (class "Default")
      (node (ref "LT5") (pin "8") (pinfunction "Gain1_8") (pintype "passive"))
    )
    (net (code "61") (name "unconnected-(LT5-Gain2-Pad5)") (class "Default")
      (node (ref "LT5") (pin "5") (pinfunction "Gain2_5") (pintype "passive"))
    )
    (net (code "62") (name "unconnected-(LT6-Gain1-Pad8)") (class "Default")
      (node (ref "LT6") (pin "8") (pinfunction "Gain1_8") (pintype "passive"))
    )
    (net (code "63") (name "unconnected-(LT6-Gain2-Pad5)") (class "Default")
      (node (ref "LT6") (pin "5") (pinfunction "Gain2_5") (pintype "passive"))
    )
    (net (code "64") (name "unconnected-(LT7-Gain1-Pad8)") (class "Default")
      (node (ref "LT7") (pin "8") (pinfunction "Gain1_8") (pintype "passive"))
    )
    (net (code "65") (name "unconnected-(LT7-Gain2-Pad5)") (class "Default")
      (node (ref "LT7") (pin "5") (pinfunction "Gain2_5") (pintype "passive"))
    )
    (net (code "66") (name "unconnected-(LT8-Gain1-Pad8)") (class "Default")
      (node (ref "LT8") (pin "8") (pinfunction "Gain1_8") (pintype "passive"))
    )
    (net (code "67") (name "unconnected-(LT8-Gain2-Pad5)") (class "Default")
      (node (ref "LT8") (pin "5") (pinfunction "Gain2_5") (pintype "passive"))
    )
    (net (code "68") (name "unconnected-(LT9-Gain1-Pad8)") (class "Default")
      (node (ref "LT9") (pin "8") (pinfunction "Gain1_8") (pintype "passive"))
    )
    (net (code "69") (name "unconnected-(LT9-Gain2-Pad5)") (class "Default")
      (node (ref "LT9") (pin "5") (pinfunction "Gain2_5") (pintype "passive"))
    )
    (net (code "70") (name "unconnected-(LT10-Gain1-Pad8)") (class "Default")
      (node (ref "LT10") (pin "8") (pinfunction "Gain1_8") (pintype "passive"))
    )
    (net (code "71") (name "unconnected-(LT10-Gain2-Pad5)") (class "Default")
      (node (ref "LT10") (pin "5") (pinfunction "Gain2_5") (pintype "passive"))
    )
    (net (code "72") (name "unconnected-(LT11-Gain1-Pad8)") (class "Default")
      (node (ref "LT11") (pin "8") (pinfunction "Gain1_8") (pintype "passive"))
    )
    (net (code "73") (name "unconnected-(LT11-Gain2-Pad5)") (class "Default")
      (node (ref "LT11") (pin "5") (pinfunction "Gain2_5") (pintype "passive"))
    )
    (net (code "74") (name "unconnected-(LT12-Gain1-Pad8)") (class "Default")
      (node (ref "LT12") (pin "8") (pinfunction "Gain1_8") (pintype "passive"))
    )
    (net (code "75") (name "unconnected-(LT12-Gain2-Pad5)") (class "Default")
      (node (ref "LT12") (pin "5") (pinfunction "Gain2_5") (pintype "passive"))
    )
    (net (code "76") (name "unconnected-(LT13-Gain1-Pad8)") (class "Default")
      (node (ref "LT13") (pin "8") (pinfunction "Gain1_8") (pintype "passive"))
    )
    (net (code "77") (name "unconnected-(LT13-Gain2-Pad5)") (class "Default")
      (node (ref "LT13") (pin "5") (pinfunction "Gain2_5") (pintype "passive"))
    )
    (net (code "78") (name "unconnected-(LT14-Gain1-Pad8)") (class "Default")
      (node (ref "LT14") (pin "8") (pinfunction "Gain1_8") (pintype "passive"))
    )
    (net (code "79") (name "unconnected-(LT14-Gain2-Pad5)") (class "Default")
      (node (ref "LT14") (pin "5") (pinfunction "Gain2_5") (pintype "passive"))
    )
    (net (code "80") (name "unconnected-(LT15-Gain1-Pad8)") (class "Default")
      (node (ref "LT15") (pin "8") (pinfunction "Gain1_8") (pintype "passive"))
    )
    (net (code "81") (name "unconnected-(LT15-Gain2-Pad5)") (class "Default")
      (node (ref "LT15") (pin "5") (pinfunction "Gain2_5") (pintype "passive"))
    )
    (net (code "82") (name "unconnected-(LT16-Gain1-Pad8)") (class "Default")
      (node (ref "LT16") (pin "8") (pinfunction "Gain1_8") (pintype "passive"))
    )
    (net (code "83") (name "unconnected-(LT16-Gain2-Pad5)") (class "Default")
      (node (ref "LT16") (pin "5") (pinfunction "Gain2_5") (pintype "passive"))
    )
  )
)
